# blade-plate-head.net
KiCad netlist of a schematic drawn in EAGLE
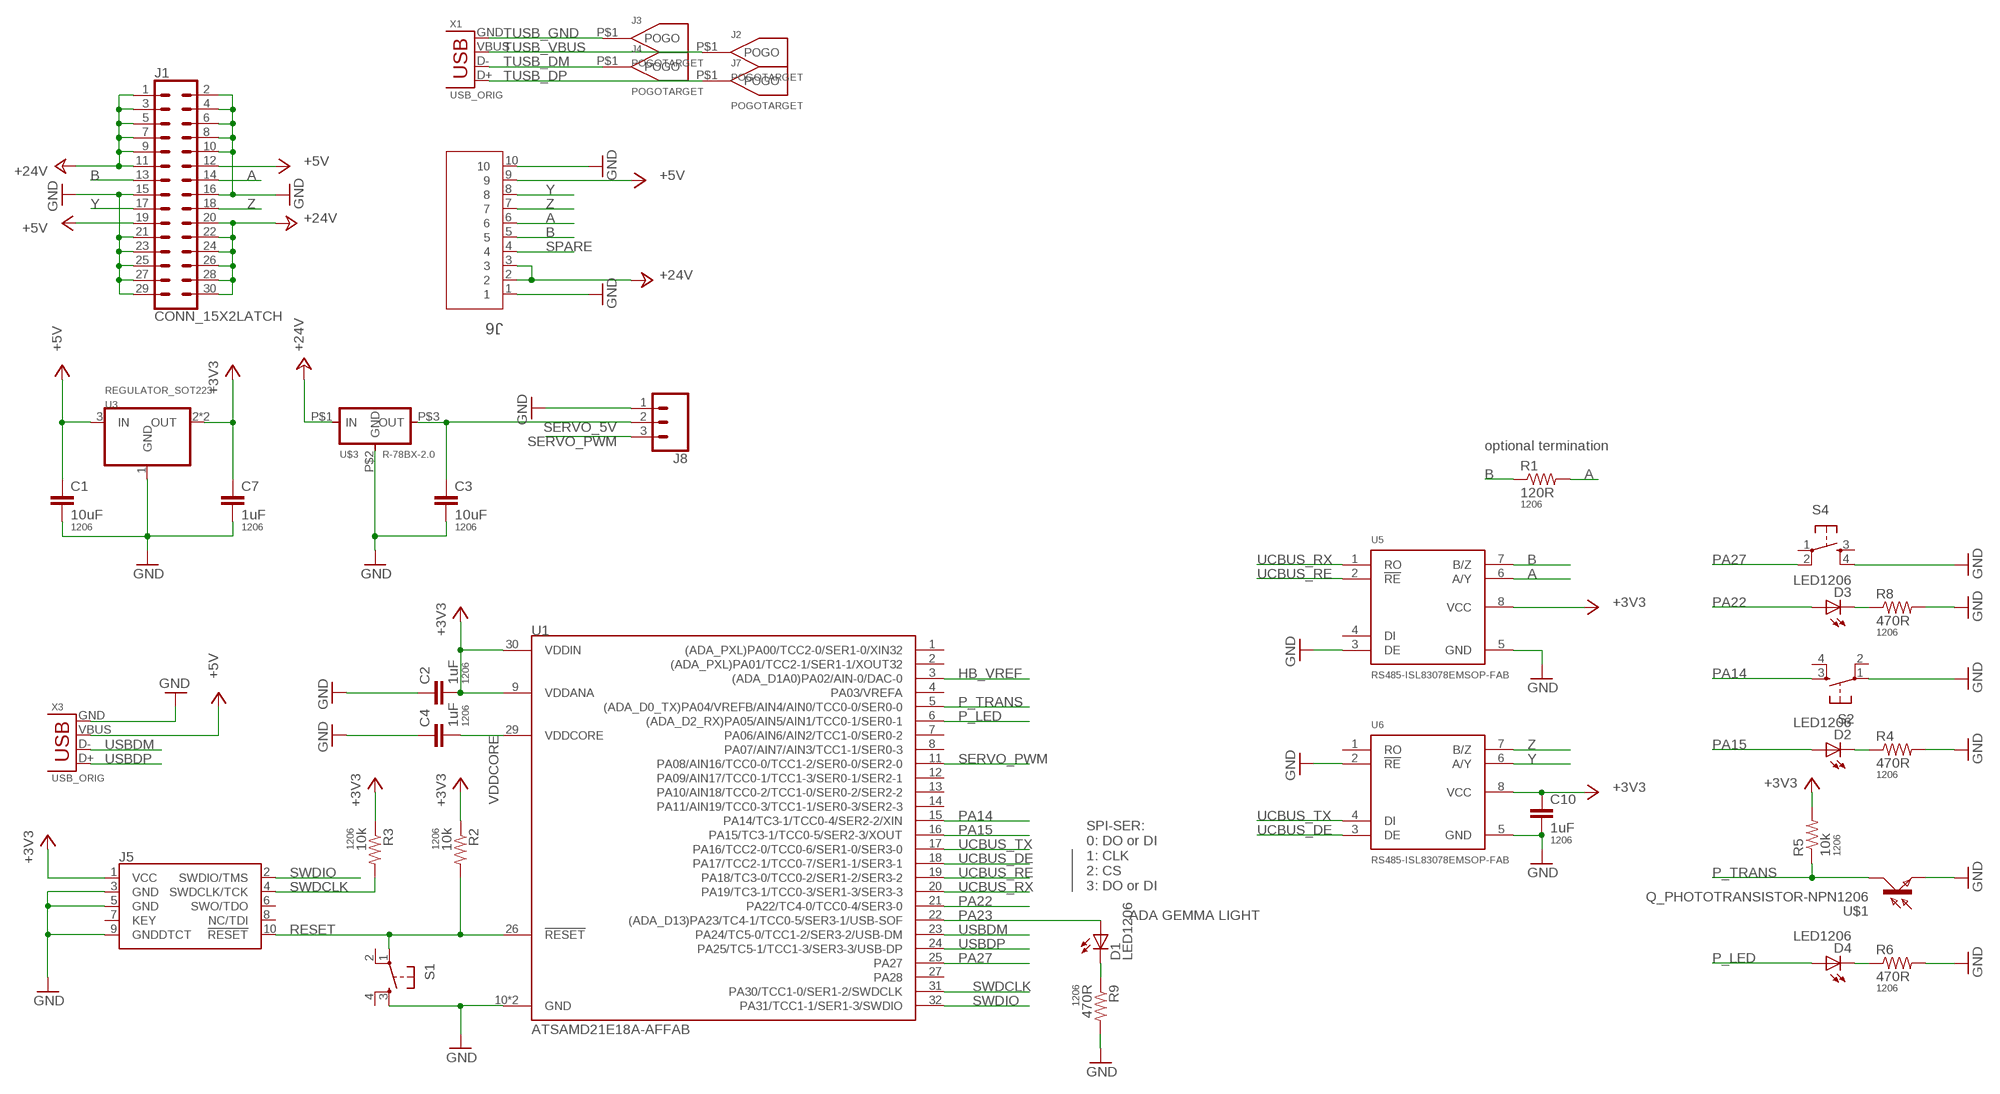
[diagram p0: schematic, sheet 1]

(export (version "E")
  (design (tool "Eeschema 10.0.6"))
  (components
    (comp (ref "C1")
      (value "10uF")
      (footprint "eagle-import:1206")
      (fields (field (name "PACKAGE") "1206"))
      (libsource (lib "eagle-import") (part "CAP1206"))
    )
    (comp (ref "C2")
      (value "1uF")
      (footprint "eagle-import:1206")
      (fields (field (name "PACKAGE") "1206"))
      (libsource (lib "eagle-import") (part "CAP1206"))
    )
    (comp (ref "C3")
      (value "10uF")
      (footprint "eagle-import:1206")
      (fields (field (name "PACKAGE") "1206"))
      (libsource (lib "eagle-import") (part "CAP1206"))
    )
    (comp (ref "C4")
      (value "1uF")
      (footprint "eagle-import:1206")
      (fields (field (name "PACKAGE") "1206"))
      (libsource (lib "eagle-import") (part "CAP1206"))
    )
    (comp (ref "C7")
      (value "1uF")
      (footprint "eagle-import:1206")
      (fields (field (name "PACKAGE") "1206"))
      (libsource (lib "eagle-import") (part "CAP1206"))
    )
    (comp (ref "C10")
      (value "1uF")
      (footprint "eagle-import:1206")
      (fields (field (name "PACKAGE") "1206"))
      (libsource (lib "eagle-import") (part "CAP1206"))
    )
    (comp (ref "D1")
      (value "LED1206")
      (footprint "eagle-import:LED1206")
      (libsource (lib "eagle-import") (part "LED1206"))
    )
    (comp (ref "D2")
      (value "LED1206")
      (footprint "eagle-import:LED1206")
      (libsource (lib "eagle-import") (part "LED1206"))
    )
    (comp (ref "D3")
      (value "LED1206")
      (footprint "eagle-import:LED1206")
      (libsource (lib "eagle-import") (part "LED1206"))
    )
    (comp (ref "D4")
      (value "LED1206")
      (footprint "eagle-import:LED1206")
      (libsource (lib "eagle-import") (part "LED1206"))
    )
    (comp (ref "J1")
      (value "CONN_15X2LATCH")
      (footprint "eagle-import:2X15-SHROUDED_LATCH")
      (libsource (lib "eagle-import") (part "CONN_15X2LATCH"))
    )
    (comp (ref "J2")
      (value "POGOTARGET")
      (footprint "eagle-import:POGO_TARGET")
      (libsource (lib "eagle-import") (part "POGOTARGET"))
    )
    (comp (ref "J3")
      (value "POGOTARGET")
      (footprint "eagle-import:POGO_TARGET")
      (libsource (lib "eagle-import") (part "POGOTARGET"))
    )
    (comp (ref "J4")
      (value "POGOTARGET")
      (footprint "eagle-import:POGO_TARGET")
      (libsource (lib "eagle-import") (part "POGOTARGET"))
    )
    (comp (ref "J5")
      (value "CORTEX_JTAG_DEBUG_PTH_NS")
      (footprint "eagle-import:2X5-PTH-1.27MM-NO_SILK")
      (libsource (lib "eagle-import") (part "CORTEX_JTAG_DEBUG_PTH_NS"))
    )
    (comp (ref "J6")
      (value "BLADE_10P_SCKT_1-1674231-1")
      (footprint "eagle-import:TE_1-1674231-1")
      (fields (field (name "COMMENT") "1-1674231-1") (field (name "MF") "TE Connectivity"))
      (libsource (lib "eagle-import") (part "BLADE_10P_SCKT_1-1674231-1"))
    )
    (comp (ref "J7")
      (value "POGOTARGET")
      (footprint "eagle-import:POGO_TARGET")
      (libsource (lib "eagle-import") (part "POGOTARGET"))
    )
    (comp (ref "J8")
      (value "CONN_03LOCK_NO_SILK")
      (footprint "eagle-import:1X03_LOCK_NO_SILK")
      (libsource (lib "eagle-import") (part "CONN_03LOCK_NO_SILK"))
    )
    (comp (ref "R1")
      (value "120R")
      (footprint "eagle-import:1206")
      (fields (field (name "PACKAGE") "1206"))
      (libsource (lib "eagle-import") (part "RESISTOR1206"))
    )
    (comp (ref "R2")
      (value "10k")
      (footprint "eagle-import:1206")
      (fields (field (name "PACKAGE") "1206"))
      (libsource (lib "eagle-import") (part "RESISTOR1206"))
    )
    (comp (ref "R3")
      (value "10k")
      (footprint "eagle-import:1206")
      (fields (field (name "PACKAGE") "1206"))
      (libsource (lib "eagle-import") (part "RESISTOR1206"))
    )
    (comp (ref "R4")
      (value "470R")
      (footprint "eagle-import:1206")
      (fields (field (name "PACKAGE") "1206"))
      (libsource (lib "eagle-import") (part "RESISTOR1206"))
    )
    (comp (ref "R5")
      (value "10k")
      (footprint "eagle-import:1206")
      (fields (field (name "PACKAGE") "1206"))
      (libsource (lib "eagle-import") (part "RESISTOR1206"))
    )
    (comp (ref "R6")
      (value "470R")
      (footprint "eagle-import:1206")
      (fields (field (name "PACKAGE") "1206"))
      (libsource (lib "eagle-import") (part "RESISTOR1206"))
    )
    (comp (ref "R8")
      (value "470R")
      (footprint "eagle-import:1206")
      (fields (field (name "PACKAGE") "1206"))
      (libsource (lib "eagle-import") (part "RESISTOR1206"))
    )
    (comp (ref "R9")
      (value "470R")
      (footprint "eagle-import:1206")
      (fields (field (name "PACKAGE") "1206"))
      (libsource (lib "eagle-import") (part "RESISTOR1206"))
    )
    (comp (ref "S1")
      (value "SW_SWITCH_TACTILE_6MM6MM_SWITCH")
      (footprint "eagle-import:6MM_SWITCH")
      (libsource (lib "eagle-import") (part "SW_SWITCH_TACTILE_6MM6MM_SWITCH"))
    )
    (comp (ref "S2")
      (value "SW_SWITCH_TACTILE_6MM6MM_SWITCH")
      (footprint "eagle-import:6MM_SWITCH")
      (libsource (lib "eagle-import") (part "SW_SWITCH_TACTILE_6MM6MM_SWITCH"))
    )
    (comp (ref "S4")
      (value "SW_SWITCH_TACTILE_6MM6MM_SWITCH")
      (footprint "eagle-import:6MM_SWITCH")
      (libsource (lib "eagle-import") (part "SW_SWITCH_TACTILE_6MM6MM_SWITCH"))
    )
    (comp (ref "U$1")
      (value "Q_PHOTOTRANSISTOR-NPN1206")
      (footprint "eagle-import:OP1206")
      (libsource (lib "eagle-import") (part "Q_PHOTOTRANSISTOR-NPN1206"))
    )
    (comp (ref "U$3")
      (value "R-78BX-2.0")
      (footprint "eagle-import:R-78BX-2.0")
      (libsource (lib "eagle-import") (part "R-78BX-2.0"))
    )
    (comp (ref "U1")
      (value "ATSAMD21E18A-AFFAB")
      (footprint "eagle-import:TQFP-32-FAB")
      (libsource (lib "eagle-import") (part "ATSAMD21E18A-AFFAB"))
    )
    (comp (ref "U3")
      (value "REGULATOR_SOT223")
      (footprint "eagle-import:SOT223")
      (libsource (lib "eagle-import") (part "REGULATOR_SOT223"))
    )
    (comp (ref "U5")
      (value "RS485-ISL83078EMSOP-FAB")
      (footprint "eagle-import:8-MSOP-FAB")
      (libsource (lib "eagle-import") (part "RS485-ISL83078EMSOP-FAB"))
    )
    (comp (ref "U6")
      (value "RS485-ISL83078EMSOP-FAB")
      (footprint "eagle-import:8-MSOP-FAB")
      (libsource (lib "eagle-import") (part "RS485-ISL83078EMSOP-FAB"))
    )
    (comp (ref "X1")
      (value "USB_ORIG")
      (footprint "eagle-import:DX4R005HJ5")
      (libsource (lib "eagle-import") (part "USB_ORIG"))
    )
    (comp (ref "X3")
      (value "USB_ORIG")
      (footprint "eagle-import:DX4R005HJ5")
      (libsource (lib "eagle-import") (part "USB_ORIG"))
    )
  )
  (nets
    (net (code "1") (name "+3V3") (class "Default")
      (node (ref "C10") (pin "1") (pinfunction "1_1") (pintype "passive"))
      (node (ref "C2") (pin "2") (pinfunction "2_2") (pintype "passive"))
      (node (ref "C7") (pin "1") (pinfunction "1_1") (pintype "passive"))
      (node (ref "J5") (pin "1") (pinfunction "VCC_1") (pintype "bidirectional"))
      (node (ref "R2") (pin "1") (pinfunction "1_1") (pintype "passive"))
      (node (ref "R3") (pin "1") (pinfunction "1_1") (pintype "passive"))
      (node (ref "R5") (pin "2") (pinfunction "2_2") (pintype "passive"))
      (node (ref "U1") (pin "30") (pinfunction "VDDIN_30") (pintype "power_in"))
      (node (ref "U1") (pin "9") (pinfunction "VDDANA_9") (pintype "power_in"))
      (node (ref "U3") (pin "2") (pinfunction "OUT_2") (pintype "bidirectional"))
      (node (ref "U3") (pin "4") (pinfunction "OUT_4") (pintype "bidirectional"))
      (node (ref "U5") (pin "8") (pinfunction "VCC_8") (pintype "bidirectional"))
      (node (ref "U6") (pin "8") (pinfunction "VCC_8") (pintype "bidirectional"))
    )
    (net (code "2") (name "+5V") (class "Default")
      (node (ref "C1") (pin "1") (pinfunction "1_1") (pintype "passive"))
      (node (ref "J1") (pin "12") (pinfunction "12_12") (pintype "passive"))
      (node (ref "J1") (pin "19") (pinfunction "19_19") (pintype "passive"))
      (node (ref "J6") (pin "9") (pinfunction "9_9") (pintype "passive"))
      (node (ref "U3") (pin "3") (pinfunction "IN_3") (pintype "bidirectional"))
      (node (ref "X3") (pin "VBUS") (pinfunction "VBUS_VBUS") (pintype "bidirectional"))
    )
    (net (code "3") (name "+24V") (class "Default")
      (node (ref "J1") (pin "1") (pinfunction "1_1") (pintype "passive"))
      (node (ref "J1") (pin "11") (pinfunction "11_11") (pintype "passive"))
      (node (ref "J1") (pin "20") (pinfunction "20_20") (pintype "passive"))
      (node (ref "J1") (pin "22") (pinfunction "22_22") (pintype "passive"))
      (node (ref "J1") (pin "24") (pinfunction "24_24") (pintype "passive"))
      (node (ref "J1") (pin "26") (pinfunction "26_26") (pintype "passive"))
      (node (ref "J1") (pin "28") (pinfunction "28_28") (pintype "passive"))
      (node (ref "J1") (pin "3") (pinfunction "3_3") (pintype "passive"))
      (node (ref "J1") (pin "30") (pinfunction "30_30") (pintype "passive"))
      (node (ref "J1") (pin "5") (pinfunction "5_5") (pintype "passive"))
      (node (ref "J1") (pin "7") (pinfunction "7_7") (pintype "passive"))
      (node (ref "J1") (pin "9") (pinfunction "9_9") (pintype "passive"))
      (node (ref "J6") (pin "2") (pinfunction "2_2") (pintype "passive"))
      (node (ref "J6") (pin "3") (pinfunction "3_3") (pintype "passive"))
      (node (ref "U$3") (pin "P$1") (pinfunction "IN_P$1") (pintype "bidirectional"))
    )
    (net (code "4") (name "/A") (class "Default")
      (node (ref "J1") (pin "14") (pinfunction "14_14") (pintype "passive"))
      (node (ref "J6") (pin "6") (pinfunction "6_6") (pintype "passive"))
      (node (ref "R1") (pin "2") (pinfunction "2_2") (pintype "passive"))
      (node (ref "U5") (pin "6") (pinfunction "A/Y_6") (pintype "bidirectional"))
    )
    (net (code "5") (name "/B") (class "Default")
      (node (ref "J1") (pin "13") (pinfunction "13_13") (pintype "passive"))
      (node (ref "J6") (pin "5") (pinfunction "5_5") (pintype "passive"))
      (node (ref "R1") (pin "1") (pinfunction "1_1") (pintype "passive"))
      (node (ref "U5") (pin "7") (pinfunction "B/Z_7") (pintype "bidirectional"))
    )
    (net (code "6") (name "/HB_VREF") (class "Default")
      (node (ref "U1") (pin "3") (pinfunction "(ADA_D1A0)PA02/AIN-0/DAC-0_3") (pintype "bidirectional"))
    )
    (net (code "7") (name "/PA14") (class "Default")
      (node (ref "S2") (pin "3") (pinfunction "S_3") (pintype "passive"))
      (node (ref "U1") (pin "15") (pinfunction "PA14/TC3-1/TCC0-4/SER2-2/XIN_15") (pintype "bidirectional"))
    )
    (net (code "8") (name "/PA15") (class "Default")
      (node (ref "D2") (pin "1") (pinfunction "A_1") (pintype "passive"))
      (node (ref "U1") (pin "16") (pinfunction "PA15/TC3-1/TCC0-5/SER2-3/XOUT_16") (pintype "bidirectional"))
    )
    (net (code "9") (name "/PA22") (class "Default")
      (node (ref "D3") (pin "1") (pinfunction "A_1") (pintype "passive"))
      (node (ref "U1") (pin "21") (pinfunction "PA22/TC4-0/TCC0-4/SER3-0_21") (pintype "bidirectional"))
    )
    (net (code "10") (name "/PA23") (class "Default")
      (node (ref "D1") (pin "1") (pinfunction "A_1") (pintype "passive"))
      (node (ref "U1") (pin "22") (pinfunction "(ADA_D13)PA23/TC4-1/TCC0-5/SER3-1/USB-SOF_22") (pintype "bidirectional"))
    )
    (net (code "11") (name "/PA27") (class "Default")
      (node (ref "S4") (pin "2") (pinfunction "P1_2") (pintype "passive"))
      (node (ref "U1") (pin "25") (pinfunction "PA27_25") (pintype "bidirectional"))
    )
    (net (code "12") (name "/P_LED") (class "Default")
      (node (ref "D4") (pin "1") (pinfunction "A_1") (pintype "passive"))
      (node (ref "U1") (pin "6") (pinfunction "(ADA_D2_RX)PA05/AIN5/AIN1/TCC0-1/SER0-1_6") (pintype "bidirectional"))
    )
    (net (code "13") (name "/P_TRANS") (class "Default")
      (node (ref "R5") (pin "1") (pinfunction "1_1") (pintype "passive"))
      (node (ref "U$1") (pin "COLLECTOR") (pinfunction "C_COLLECTOR") (pintype "passive"))
      (node (ref "U1") (pin "5") (pinfunction "(ADA_D0_TX)PA04/VREFB/AIN4/AIN0/TCC0-0/SER0-0_5") (pintype "bidirectional"))
    )
    (net (code "14") (name "/RESET") (class "Default")
      (node (ref "J5") (pin "10") (pinfunction "~{RESET}_10") (pintype "bidirectional"))
      (node (ref "R2") (pin "2") (pinfunction "2_2") (pintype "passive"))
      (node (ref "S1") (pin "1") (pinfunction "P_1") (pintype "passive"))
      (node (ref "U1") (pin "26") (pinfunction "~{RESET}_26") (pintype "input"))
    )
    (net (code "15") (name "/SERVO_5V") (class "Default")
      (node (ref "C3") (pin "1") (pinfunction "1_1") (pintype "passive"))
      (node (ref "J8") (pin "2") (pinfunction "2_2") (pintype "passive"))
      (node (ref "U$3") (pin "P$3") (pinfunction "OUT_P$3") (pintype "bidirectional"))
    )
    (net (code "16") (name "/SERVO_PWM") (class "Default")
      (node (ref "J8") (pin "3") (pinfunction "3_3") (pintype "passive"))
      (node (ref "U1") (pin "11") (pinfunction "PA08/AIN16/TCC0-0/TCC1-2/SER0-0/SER2-0_11") (pintype "bidirectional"))
    )
    (net (code "17") (name "/SPARE") (class "Default")
      (node (ref "J6") (pin "4") (pinfunction "4_4") (pintype "passive"))
    )
    (net (code "18") (name "/SWDCLK") (class "Default")
      (node (ref "J5") (pin "4") (pinfunction "SWDCLK/TCK_4") (pintype "bidirectional"))
      (node (ref "R3") (pin "2") (pinfunction "2_2") (pintype "passive"))
      (node (ref "U1") (pin "31") (pinfunction "PA30/TCC1-0/SER1-2/SWDCLK_31") (pintype "bidirectional"))
    )
    (net (code "19") (name "/SWDIO") (class "Default")
      (node (ref "J5") (pin "2") (pinfunction "SWDIO/TMS_2") (pintype "bidirectional"))
      (node (ref "U1") (pin "32") (pinfunction "PA31/TCC1-1/SER1-3/SWDIO_32") (pintype "bidirectional"))
    )
    (net (code "20") (name "/TUSB_DM") (class "Default")
      (node (ref "J4") (pin "P$1") (pinfunction "POGO_P$1") (pintype "bidirectional"))
      (node (ref "X1") (pin "D-") (pinfunction "D-_D-") (pintype "bidirectional"))
    )
    (net (code "21") (name "/TUSB_DP") (class "Default")
      (node (ref "J7") (pin "P$1") (pinfunction "POGO_P$1") (pintype "bidirectional"))
      (node (ref "X1") (pin "D+") (pinfunction "D+_D+") (pintype "bidirectional"))
    )
    (net (code "22") (name "/TUSB_GND") (class "Default")
      (node (ref "J3") (pin "P$1") (pinfunction "POGO_P$1") (pintype "bidirectional"))
      (node (ref "X1") (pin "GND") (pinfunction "GND_GND") (pintype "bidirectional"))
    )
    (net (code "23") (name "/TUSB_VBUS") (class "Default")
      (node (ref "J2") (pin "P$1") (pinfunction "POGO_P$1") (pintype "bidirectional"))
      (node (ref "X1") (pin "VBUS") (pinfunction "VBUS_VBUS") (pintype "bidirectional"))
    )
    (net (code "24") (name "/UCBUS_DE") (class "Default")
      (node (ref "U1") (pin "18") (pinfunction "PA17/TCC2-1/TCC0-7/SER1-1/SER3-1_18") (pintype "bidirectional"))
      (node (ref "U6") (pin "3") (pinfunction "DE_3") (pintype "bidirectional"))
    )
    (net (code "25") (name "/UCBUS_RE") (class "Default")
      (node (ref "U1") (pin "19") (pinfunction "PA18/TC3-0/TCC0-2/SER1-2/SER3-2_19") (pintype "bidirectional"))
      (node (ref "U5") (pin "2") (pinfunction "~{RE}_2") (pintype "bidirectional"))
    )
    (net (code "26") (name "/UCBUS_RX") (class "Default")
      (node (ref "U1") (pin "20") (pinfunction "PA19/TC3-1/TCC0-3/SER1-3/SER3-3_20") (pintype "bidirectional"))
      (node (ref "U5") (pin "1") (pinfunction "RO_1") (pintype "bidirectional"))
    )
    (net (code "27") (name "/UCBUS_TX") (class "Default")
      (node (ref "U1") (pin "17") (pinfunction "PA16/TCC2-0/TCC0-6/SER1-0/SER3-0_17") (pintype "bidirectional"))
      (node (ref "U6") (pin "4") (pinfunction "DI_4") (pintype "bidirectional"))
    )
    (net (code "28") (name "/USBDM") (class "Default")
      (node (ref "U1") (pin "23") (pinfunction "PA24/TC5-0/TCC1-2/SER3-2/USB-DM_23") (pintype "bidirectional"))
      (node (ref "X3") (pin "D-") (pinfunction "D-_D-") (pintype "bidirectional"))
    )
    (net (code "29") (name "/USBDP") (class "Default")
      (node (ref "U1") (pin "24") (pinfunction "PA25/TC5-1/TCC1-3/SER3-3/USB-DP_24") (pintype "bidirectional"))
      (node (ref "X3") (pin "D+") (pinfunction "D+_D+") (pintype "bidirectional"))
    )
    (net (code "30") (name "/VDDCORE") (class "Default")
      (node (ref "C4") (pin "2") (pinfunction "2_2") (pintype "passive"))
      (node (ref "U1") (pin "29") (pinfunction "VDDCORE_29") (pintype "power_in"))
    )
    (net (code "31") (name "/Y") (class "Default")
      (node (ref "J1") (pin "17") (pinfunction "17_17") (pintype "passive"))
      (node (ref "J6") (pin "8") (pinfunction "8_8") (pintype "passive"))
      (node (ref "U6") (pin "6") (pinfunction "A/Y_6") (pintype "bidirectional"))
    )
    (net (code "32") (name "/Z") (class "Default")
      (node (ref "J1") (pin "18") (pinfunction "18_18") (pintype "passive"))
      (node (ref "J6") (pin "7") (pinfunction "7_7") (pintype "passive"))
      (node (ref "U6") (pin "7") (pinfunction "B/Z_7") (pintype "bidirectional"))
    )
    (net (code "33") (name "GND") (class "Default")
      (node (ref "C1") (pin "2") (pinfunction "2_2") (pintype "passive"))
      (node (ref "C10") (pin "2") (pinfunction "2_2") (pintype "passive"))
      (node (ref "C2") (pin "1") (pinfunction "1_1") (pintype "passive"))
      (node (ref "C3") (pin "2") (pinfunction "2_2") (pintype "passive"))
      (node (ref "C4") (pin "1") (pinfunction "1_1") (pintype "passive"))
      (node (ref "C7") (pin "2") (pinfunction "2_2") (pintype "passive"))
      (node (ref "J1") (pin "10") (pinfunction "10_10") (pintype "passive"))
      (node (ref "J1") (pin "15") (pinfunction "15_15") (pintype "passive"))
      (node (ref "J1") (pin "16") (pinfunction "16_16") (pintype "passive"))
      (node (ref "J1") (pin "2") (pinfunction "2_2") (pintype "passive"))
      (node (ref "J1") (pin "21") (pinfunction "21_21") (pintype "passive"))
      (node (ref "J1") (pin "23") (pinfunction "23_23") (pintype "passive"))
      (node (ref "J1") (pin "25") (pinfunction "25_25") (pintype "passive"))
      (node (ref "J1") (pin "27") (pinfunction "27_27") (pintype "passive"))
      (node (ref "J1") (pin "29") (pinfunction "29_29") (pintype "passive"))
      (node (ref "J1") (pin "4") (pinfunction "4_4") (pintype "passive"))
      (node (ref "J1") (pin "6") (pinfunction "6_6") (pintype "passive"))
      (node (ref "J1") (pin "8") (pinfunction "8_8") (pintype "passive"))
      (node (ref "J5") (pin "3") (pinfunction "GND_3") (pintype "bidirectional"))
      (node (ref "J5") (pin "5") (pinfunction "GND_5") (pintype "bidirectional"))
      (node (ref "J5") (pin "9") (pinfunction "GNDDTCT_9") (pintype "bidirectional"))
      (node (ref "J6") (pin "1") (pinfunction "1_1") (pintype "passive"))
      (node (ref "J6") (pin "10") (pinfunction "10_10") (pintype "passive"))
      (node (ref "J8") (pin "1") (pinfunction "1_1") (pintype "passive"))
      (node (ref "R4") (pin "2") (pinfunction "2_2") (pintype "passive"))
      (node (ref "R6") (pin "2") (pinfunction "2_2") (pintype "passive"))
      (node (ref "R8") (pin "2") (pinfunction "2_2") (pintype "passive"))
      (node (ref "R9") (pin "2") (pinfunction "2_2") (pintype "passive"))
      (node (ref "S1") (pin "3") (pinfunction "S_3") (pintype "passive"))
      (node (ref "S2") (pin "1") (pinfunction "P_1") (pintype "passive"))
      (node (ref "S4") (pin "4") (pinfunction "S1_4") (pintype "passive"))
      (node (ref "U$1") (pin "EMITTER") (pinfunction "E_EMITTER") (pintype "passive"))
      (node (ref "U$3") (pin "P$2") (pinfunction "GND_P$2") (pintype "bidirectional"))
      (node (ref "U1") (pin "10") (pinfunction "GND_10") (pintype "power_in"))
      (node (ref "U1") (pin "28") (pinfunction "GND_28") (pintype "power_in"))
      (node (ref "U3") (pin "1") (pinfunction "GND_1") (pintype "bidirectional"))
      (node (ref "U5") (pin "3") (pinfunction "DE_3") (pintype "bidirectional"))
      (node (ref "U5") (pin "5") (pinfunction "GND_5") (pintype "bidirectional"))
      (node (ref "U6") (pin "2") (pinfunction "~{RE}_2") (pintype "bidirectional"))
      (node (ref "U6") (pin "5") (pinfunction "GND_5") (pintype "bidirectional"))
      (node (ref "X3") (pin "GND") (pinfunction "GND_GND") (pintype "bidirectional"))
    )
    (net (code "34") (name "Net-(D1-C)") (class "Default")
      (node (ref "D1") (pin "2") (pinfunction "C_2") (pintype "passive"))
      (node (ref "R9") (pin "1") (pinfunction "1_1") (pintype "passive"))
    )
    (net (code "35") (name "Net-(D2-C)") (class "Default")
      (node (ref "D2") (pin "2") (pinfunction "C_2") (pintype "passive"))
      (node (ref "R4") (pin "1") (pinfunction "1_1") (pintype "passive"))
    )
    (net (code "36") (name "Net-(D3-C)") (class "Default")
      (node (ref "D3") (pin "2") (pinfunction "C_2") (pintype "passive"))
      (node (ref "R8") (pin "1") (pinfunction "1_1") (pintype "passive"))
    )
    (net (code "37") (name "Net-(D4-C)") (class "Default")
      (node (ref "D4") (pin "2") (pinfunction "C_2") (pintype "passive"))
      (node (ref "R6") (pin "1") (pinfunction "1_1") (pintype "passive"))
    )
    (net (code "38") (name "unconnected-(J5-KEY-Pad7)") (class "Default")
      (node (ref "J5") (pin "7") (pinfunction "KEY_7") (pintype "bidirectional"))
    )
    (net (code "39") (name "unconnected-(J5-NC{slash}TDI-Pad8)") (class "Default")
      (node (ref "J5") (pin "8") (pinfunction "NC/TDI_8") (pintype "bidirectional"))
    )
    (net (code "40") (name "unconnected-(J5-SWO{slash}TDO-Pad6)") (class "Default")
      (node (ref "J5") (pin "6") (pinfunction "SWO/TDO_6") (pintype "bidirectional"))
    )
    (net (code "41") (name "unconnected-(S1-P1-Pad2)") (class "Default")
      (node (ref "S1") (pin "2") (pinfunction "P1_2") (pintype "passive"))
    )
    (net (code "42") (name "unconnected-(S1-S1-Pad4)") (class "Default")
      (node (ref "S1") (pin "4") (pinfunction "S1_4") (pintype "passive"))
    )
    (net (code "43") (name "unconnected-(S2-P1-Pad2)") (class "Default")
      (node (ref "S2") (pin "2") (pinfunction "P1_2") (pintype "passive"))
    )
    (net (code "44") (name "unconnected-(S2-S1-Pad4)") (class "Default")
      (node (ref "S2") (pin "4") (pinfunction "S1_4") (pintype "passive"))
    )
    (net (code "45") (name "unconnected-(S4-P-Pad1)") (class "Default")
      (node (ref "S4") (pin "1") (pinfunction "P_1") (pintype "passive"))
    )
    (net (code "46") (name "unconnected-(S4-S-Pad3)") (class "Default")
      (node (ref "S4") (pin "3") (pinfunction "S_3") (pintype "passive"))
    )
    (net (code "47") (name "unconnected-(U1-(ADA_PXL)PA00{slash}TCC2-0{slash}SER1-0{slash}XIN32-Pad1)") (class "Default")
      (node (ref "U1") (pin "1") (pinfunction "(ADA_PXL)PA00/TCC2-0/SER1-0/XIN32_1") (pintype "bidirectional"))
    )
    (net (code "48") (name "unconnected-(U1-(ADA_PXL)PA01{slash}TCC2-1{slash}SER1-1{slash}XOUT32-Pad2)") (class "Default")
      (node (ref "U1") (pin "2") (pinfunction "(ADA_PXL)PA01/TCC2-1/SER1-1/XOUT32_2") (pintype "bidirectional"))
    )
    (net (code "49") (name "unconnected-(U1-PA03{slash}VREFA-Pad4)") (class "Default")
      (node (ref "U1") (pin "4") (pinfunction "PA03/VREFA_4") (pintype "bidirectional"))
    )
    (net (code "50") (name "unconnected-(U1-PA06{slash}AIN6{slash}AIN2{slash}TCC1-0{slash}SER0-2-Pad7)") (class "Default")
      (node (ref "U1") (pin "7") (pinfunction "PA06/AIN6/AIN2/TCC1-0/SER0-2_7") (pintype "bidirectional"))
    )
    (net (code "51") (name "unconnected-(U1-PA07{slash}AIN7{slash}AIN3{slash}TCC1-1{slash}SER0-3-Pad8)") (class "Default")
      (node (ref "U1") (pin "8") (pinfunction "PA07/AIN7/AIN3/TCC1-1/SER0-3_8") (pintype "bidirectional"))
    )
    (net (code "52") (name "unconnected-(U1-PA09{slash}AIN17{slash}TCC0-1{slash}TCC1-3{slash}SER0-1{slash}SER2-1-Pad12)") (class "Default")
      (node (ref "U1") (pin "12") (pinfunction "PA09/AIN17/TCC0-1/TCC1-3/SER0-1/SER2-1_12") (pintype "bidirectional"))
    )
    (net (code "53") (name "unconnected-(U1-PA10{slash}AIN18{slash}TCC0-2{slash}TCC1-0{slash}SER0-2{slash}SER2-2-Pad13)") (class "Default")
      (node (ref "U1") (pin "13") (pinfunction "PA10/AIN18/TCC0-2/TCC1-0/SER0-2/SER2-2_13") (pintype "bidirectional"))
    )
    (net (code "54") (name "unconnected-(U1-PA11{slash}AIN19{slash}TCC0-3{slash}TCC1-1{slash}SER0-3{slash}SER2-3-Pad14)") (class "Default")
      (node (ref "U1") (pin "14") (pinfunction "PA11/AIN19/TCC0-3/TCC1-1/SER0-3/SER2-3_14") (pintype "bidirectional"))
    )
    (net (code "55") (name "unconnected-(U1-PA28-Pad27)") (class "Default")
      (node (ref "U1") (pin "27") (pinfunction "PA28_27") (pintype "bidirectional"))
    )
    (net (code "56") (name "unconnected-(U5-DI-Pad4)") (class "Default")
      (node (ref "U5") (pin "4") (pinfunction "DI_4") (pintype "bidirectional"))
    )
    (net (code "57") (name "unconnected-(U6-RO-Pad1)") (class "Default")
      (node (ref "U6") (pin "1") (pinfunction "RO_1") (pintype "bidirectional"))
    )
  )
)
